# Sensors.net
KiCad netlist of a schematic drawn in Altium Designer
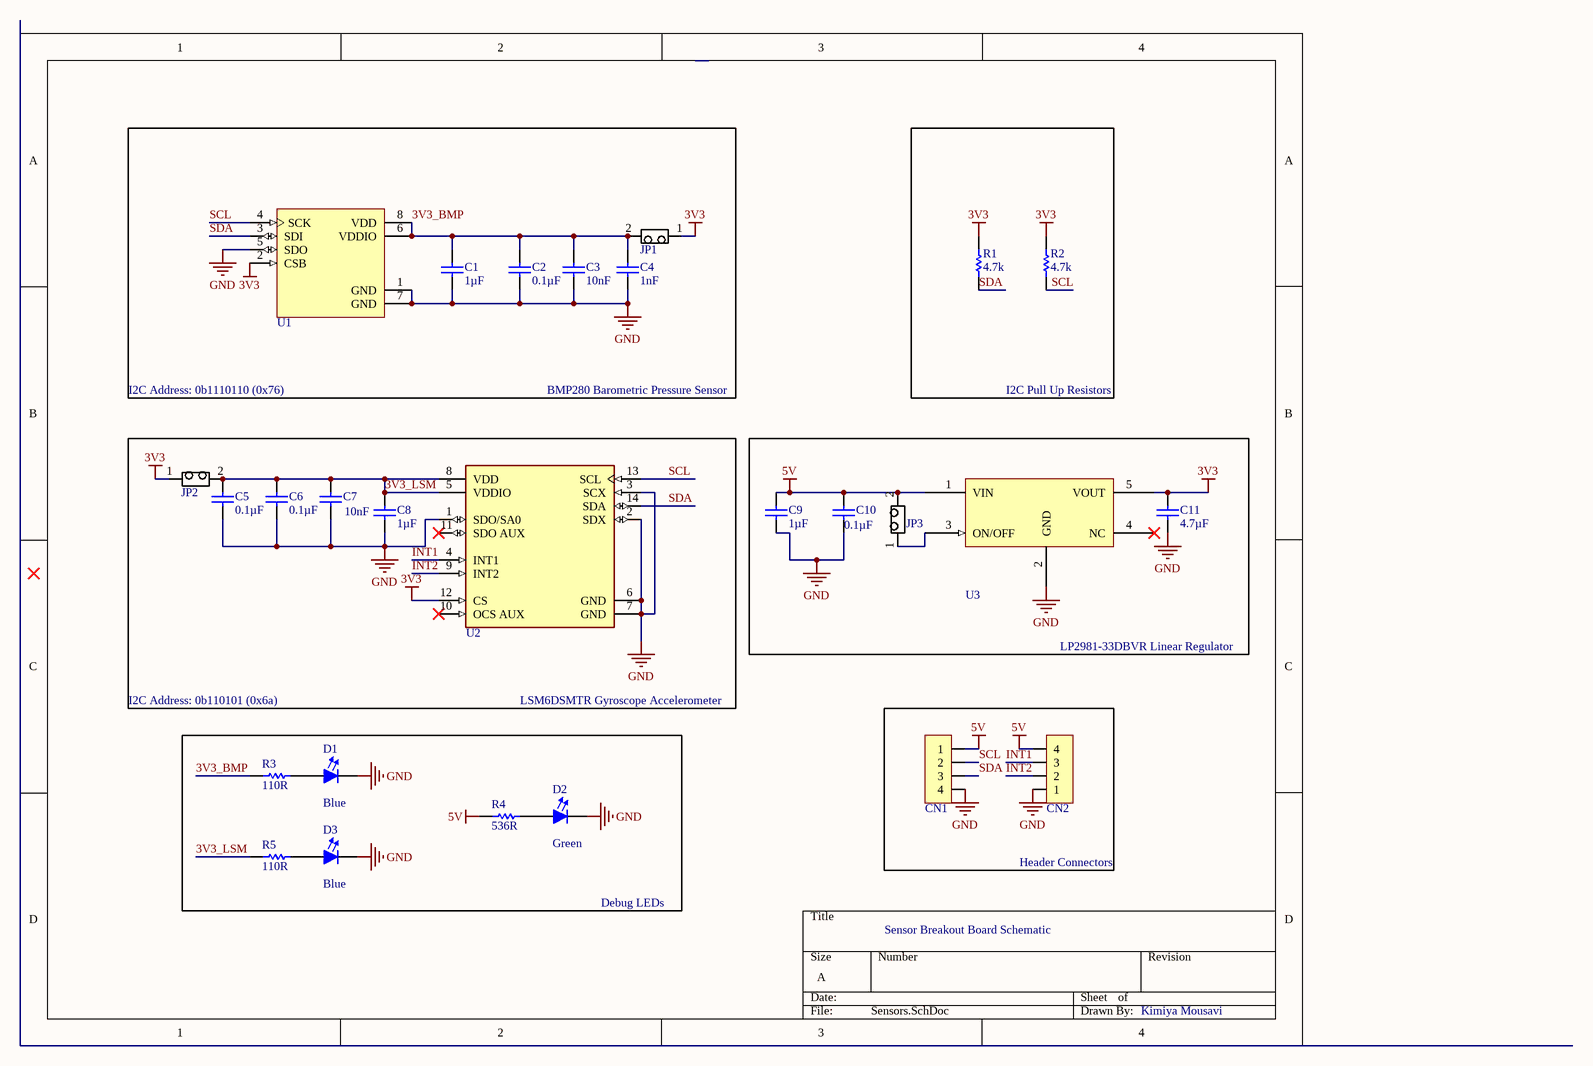
[diagram p0: Sensors.SchDoc]

(export (version "E")
  (design (tool "Eeschema 10.0.6"))
  (components
    (comp (ref "C1")
      (value "1µF")
      (footprint "CAPC1608N(0603\")")
      (description "Capacitor, Ceramic, 25V, +/- 10%, 0603 SMD, X5R")
      (fields
        (field (name "MFG") "Murata-Electronics-North-America")
        (field (name "Comment") "1uF 25V 0603 SMD, Ceramic")
        (field (name "CREATED BY") "Andy Bates")
        (field (name "PUBLISHER") "AUVic")
      )
      (libsource (lib "AUVIC") (part "Symbol"))
    )
    (comp (ref "C2")
      (value "0.1uF, 50V, 10%, X7R, 0603")
      (footprint "CAPC1608N(0603\")")
      (description "0.1µF ±10% Ceramic Capacitor X7R 0603 (1608 Metric)")
      (fields (field (name "CAPACITANCE") "0.1µF") (field (name "CREATED BY") "Poorna Chander Kalidas"))
      (libsource (lib "AUVIC") (part "Symbol"))
    )
    (comp (ref "C3")
      (value "10nF")
      (footprint "CAPC1608N(0603\")")
      (description "Capacitor, Ceramic, 50V, +/- 10%, 0603 SMD")
      (fields
        (field (name "MFG") "Samsung")
        (field (name "Comment") "10 nF, 50V 0603 SMD, Ceramic")
        (field (name "CREATED BY") "Gabriel")
        (field (name "PUBLISHER") "AUVic")
      )
      (libsource (lib "AUVIC") (part "Symbol"))
    )
    (comp (ref "C4")
      (value "1nF")
      (footprint "CAPC1608N(0603\")")
      (description "Capacitor, Ceramic, 50V, +-1%, 0603 SMD, NP0")
      (fields
        (field (name "Comment") "1nF, Ceramic, 50V, +-1%, SMD, NP0")
        (field (name "PUBLISHER") "AUVic")
        (field (name "MADE BY") "Jordan Day")
      )
      (libsource (lib "AUVIC") (part "Symbol"))
    )
    (comp (ref "C5")
      (value "0.1uF, 50V, 10%, X7R, 0603")
      (footprint "CAPC1608N(0603\")")
      (description "0.1µF ±10% Ceramic Capacitor X7R 0603 (1608 Metric)")
      (fields (field (name "CAPACITANCE") "0.1µF") (field (name "CREATED BY") "Poorna Chander Kalidas"))
      (libsource (lib "AUVIC") (part "Symbol"))
    )
    (comp (ref "C6")
      (value "0.1uF, 50V, 10%, X7R, 0603")
      (footprint "CAPC1608N(0603\")")
      (description "0.1µF ±10% Ceramic Capacitor X7R 0603 (1608 Metric)")
      (fields (field (name "CAPACITANCE") "0.1µF") (field (name "CREATED BY") "Poorna Chander Kalidas"))
      (libsource (lib "AUVIC") (part "Symbol"))
    )
    (comp (ref "C7")
      (value "10nF")
      (footprint "CAPC1608N(0603\")")
      (description "Capacitor, Ceramic, 50V, +/- 10%, 0603 SMD")
      (fields
        (field (name "MFG") "Samsung")
        (field (name "Comment") "10 nF, 50V 0603 SMD, Ceramic")
        (field (name "CREATED BY") "Gabriel")
        (field (name "PUBLISHER") "AUVic")
      )
      (libsource (lib "AUVIC") (part "Symbol"))
    )
    (comp (ref "C8")
      (value "1µF")
      (footprint "CAPC1608N(0603\")")
      (description "Capacitor, Ceramic, 25V, +/- 10%, 0603 SMD, X5R")
      (fields
        (field (name "MFG") "Murata-Electronics-North-America")
        (field (name "Comment") "1uF 25V 0603 SMD, Ceramic")
        (field (name "CREATED BY") "Andy Bates")
        (field (name "PUBLISHER") "AUVic")
      )
      (libsource (lib "AUVIC") (part "Symbol"))
    )
    (comp (ref "C9")
      (value "1µF")
      (footprint "CAPC1608N(0603\")")
      (description "Capacitor, Ceramic, 25V, +/- 10%, 0603 SMD, X5R")
      (fields
        (field (name "MFG") "Murata-Electronics-North-America")
        (field (name "Comment") "1uF 25V 0603 SMD, Ceramic")
        (field (name "CREATED BY") "Andy Bates")
        (field (name "PUBLISHER") "AUVic")
      )
      (libsource (lib "AUVIC") (part "Symbol"))
    )
    (comp (ref "C10")
      (value "0.1µF")
      (footprint "CAPC1608N(0603\")")
      (description "Capacitor, Ceramic, 16V, +/- 10%, 0603 SMD, X7R")
      (fields
        (field (name "Comment") "0.1uF 16V 0603 SMD, Ceramic")
        (field (name "CREATED BY") "Andy Bates")
        (field (name "PUBLISHER") "AUVic")
      )
      (libsource (lib "AUVIC") (part "Symbol"))
    )
    (comp (ref "C11")
      (value "4.7µF")
      (footprint "CAPC1608N(0603\")")
      (description "Capacitor, Ceramic, 10V, +/- 10%, 0603 SMD, X5R")
      (fields
        (field (name "MFG") "Samsung")
        (field (name "Comment") "4.7uF 10V 0603 SMD, Ceramic")
        (field (name "CREATED BY") "Ashwin Sira")
        (field (name "PUBLISHER") "AUVic")
      )
      (libsource (lib "AUVIC") (part "Symbol"))
    )
    (comp (ref "CN1")
      (value "Header, Male, 1x4")
      (footprint "Header, Male, 1X4")
      (description "1x4, Pads Pitch: 0.1\" (2.54mm), Through hole")
      (libsource (lib "") (part "Symbol_3"))
    )
    (comp (ref "CN2")
      (value "Header, Male, 1x4")
      (footprint "Header, Male, 1X4")
      (description "1x4, Pads Pitch: 0.1\" (2.54mm), Through hole")
      (libsource (lib "") (part "Symbol_4"))
    )
    (comp (ref "D1")
      (value "LBQ39E-N1OO-35-1")
      (footprint "FP-LB_Q39E-MFG")
      (description "LED BLUE DIFFUSED 0603 SMD")
      (fields (field (name "COLOR") "Blue"))
      (libsource (lib "") (part "Symbol_1"))
    )
    (comp (ref "D2")
      (value "LT Q39G-Q1OO-25-1")
      (footprint "FP-LB_Q39E-MFG")
      (description "LED GREEN DIFFUSED 0603 SMD")
      (fields (field (name "COLOR") "Green"))
      (libsource (lib "") (part "Symbol_1"))
    )
    (comp (ref "D3")
      (value "LBQ39E-N1OO-35-1")
      (footprint "FP-LB_Q39E-MFG")
      (description "LED BLUE DIFFUSED 0603 SMD")
      (fields (field (name "COLOR") "Blue"))
      (libsource (lib "") (part "Symbol_1"))
    )
    (comp (ref "JP1")
      (value "1x2 Male Header")
      (footprint "2X1 Males Header")
      (fields (field (name "MADE BY") "Andy Bates"))
      (libsource (lib "AUVIC") (part "1x2 Male Header"))
    )
    (comp (ref "JP2")
      (value "1x2 Male Header")
      (footprint "2X1 Males Header")
      (fields (field (name "MADE BY") "Andy Bates"))
      (libsource (lib "AUVIC") (part "1x2 Male Header"))
    )
    (comp (ref "JP3")
      (value "1x2 Male Header")
      (footprint "2X1 Males Header")
      (fields (field (name "MADE BY") "Andy Bates"))
      (libsource (lib "AUVIC") (part "1x2 Male Header"))
    )
    (comp (ref "R1")
      (value "4.7k")
      (footprint "RESC1608N(0603\")")
      (description "4.7kR, 1%, 1/8W, 0603 SMD")
      (fields (field (name "MADE BY") "Ashwin Sira"))
      (libsource (lib "") (part "Symbol_2"))
    )
    (comp (ref "R2")
      (value "4.7k")
      (footprint "RESC1608N(0603\")")
      (description "4.7kR, 1%, 1/8W, 0603 SMD")
      (fields (field (name "MADE BY") "Ashwin Sira"))
      (libsource (lib "") (part "Symbol_2"))
    )
    (comp (ref "R3")
      (value "RC0603FR-07110RL")
      (footprint "RESC1608X55X25ML10T15")
      (description "RES SMD 110 OHM 1% 1/10W 0603")
      (fields (field (name "TOLERANCE") "1%") (field (name "RESISTANCE") "110R"))
      (libsource (lib "AUVIC") (part "RES"))
    )
    (comp (ref "R4")
      (value "ERJ-3EKF5360V")
      (footprint "RESC1608X55X30LL15T15")
      (description "SMD Chip Resistor, 0603 [1608 Metric], 536 ohm, ERJ3EK Series, 75 V, Thick Film, 100 mW")
      (fields (field (name "TOLERANCE") "1%") (field (name "RESISTANCE") "536R"))
      (libsource (lib "AUVIC") (part "RES"))
    )
    (comp (ref "R5")
      (value "RC0603FR-07110RL")
      (footprint "RESC1608X55X25ML10T15")
      (description "RES SMD 110 OHM 1% 1/10W 0603")
      (fields (field (name "TOLERANCE") "1%") (field (name "RESISTANCE") "110R"))
      (libsource (lib "AUVIC") (part "RES"))
    )
    (comp (ref "U1")
      (value "BMP280 Barometric Pressure Sensor")
      (footprint "BOSC-LGA-8_V")
      (description "BMP280 Absolute Barometric Pressure Sensor for Battery Powered Devices 2 x 2.5mm")
      (libsource (lib "AUVIC") (part "BOSC-BMP280-LGA-8"))
    )
    (comp (ref "U2")
      (value "LSM6DSMTR, Accelerometer/Gyroscope, LGA-14")
      (footprint "FP-LGA-14L-DM00249496-MFG")
      (description "IMU ACCEL/GYRO I2C/SPI 14LGA")
      (libsource (lib "AUVIC") (part "dd82ae232bae541fa9c740d21cb9072"))
    )
    (comp (ref "U3")
      (value "LP2981-33DBVR")
      (footprint "SOT95P280X145-5N")
      (description "IC REG LINEAR 3.3V 100MA SOT23-5")
      (libsource (lib "AUVIC") (part "LP2981-33DBVR"))
    )
  )
  (nets
    (net (code "1") (name "/3V3_BMP") (class "Default")
      (node (ref "C1") (pin "2") (pinfunction "Cathode_2") (pintype "passive"))
      (node (ref "C2") (pin "2") (pinfunction "Cathode_2") (pintype "passive"))
      (node (ref "C3") (pin "2") (pinfunction "Cathode_2") (pintype "passive"))
      (node (ref "C4") (pin "2") (pinfunction "Cathode_2") (pintype "passive"))
      (node (ref "JP1") (pin "2") (pinfunction "2_2") (pintype "passive"))
      (node (ref "R3") (pin "1") (pinfunction "1_1") (pintype "passive"))
      (node (ref "U1") (pin "6") (pinfunction "VDDIO_6") (pintype "power_in"))
      (node (ref "U1") (pin "8") (pinfunction "VDD_8") (pintype "power_in"))
    )
    (net (code "2") (name "/3V3_LSM") (class "Default")
      (node (ref "C5") (pin "1") (pinfunction "Anode_1") (pintype "passive"))
      (node (ref "C6") (pin "1") (pinfunction "Anode_1") (pintype "passive"))
      (node (ref "C7") (pin "2") (pinfunction "Cathode_2") (pintype "passive"))
      (node (ref "C8") (pin "2") (pinfunction "Cathode_2") (pintype "passive"))
      (node (ref "JP2") (pin "2") (pinfunction "2_2") (pintype "passive"))
      (node (ref "R5") (pin "1") (pinfunction "1_1") (pintype "passive"))
      (node (ref "U2") (pin "5") (pinfunction "VDDIO_5") (pintype "power_in"))
      (node (ref "U2") (pin "8") (pinfunction "VDD_8") (pintype "power_in"))
    )
    (net (code "3") (name "/INT1") (class "Default")
      (node (ref "CN2") (pin "3") (pinfunction "3_3") (pintype "passive"))
      (node (ref "U2") (pin "4") (pinfunction "INT1_4") (pintype "input"))
    )
    (net (code "4") (name "/INT2") (class "Default")
      (node (ref "CN2") (pin "2") (pinfunction "2_2") (pintype "passive"))
      (node (ref "U2") (pin "9") (pinfunction "INT2_9") (pintype "input"))
    )
    (net (code "5") (name "/SCL") (class "Default")
      (node (ref "CN1") (pin "2") (pinfunction "2_2") (pintype "passive"))
      (node (ref "R2") (pin "1") (pinfunction "1_1") (pintype "passive"))
      (node (ref "U1") (pin "4") (pinfunction "SCK_4") (pintype "input"))
      (node (ref "U2") (pin "13") (pinfunction "SCL_13") (pintype "input"))
    )
    (net (code "6") (name "/SDA") (class "Default")
      (node (ref "CN1") (pin "3") (pinfunction "3_3") (pintype "passive"))
      (node (ref "R1") (pin "1") (pinfunction "1_1") (pintype "passive"))
      (node (ref "U1") (pin "3") (pinfunction "SDI_3") (pintype "bidirectional"))
      (node (ref "U2") (pin "14") (pinfunction "SDA_14") (pintype "bidirectional"))
    )
    (net (code "7") (name "3V3") (class "Default")
      (node (ref "C11") (pin "2") (pinfunction "Cathode_2") (pintype "passive"))
      (node (ref "JP1") (pin "1") (pinfunction "1_1") (pintype "passive"))
      (node (ref "JP2") (pin "1") (pinfunction "1_1") (pintype "passive"))
      (node (ref "R1") (pin "2") (pinfunction "2_2") (pintype "passive"))
      (node (ref "R2") (pin "2") (pinfunction "2_2") (pintype "passive"))
      (node (ref "U1") (pin "2") (pinfunction "CSB_2") (pintype "input"))
      (node (ref "U2") (pin "12") (pinfunction "CS_12") (pintype "input"))
      (node (ref "U3") (pin "5") (pinfunction "VOUT_5") (pintype "power_in"))
    )
    (net (code "8") (name "5V") (class "Default")
      (node (ref "C10") (pin "2") (pinfunction "Cathode_2") (pintype "passive"))
      (node (ref "C9") (pin "2") (pinfunction "Cathode_2") (pintype "passive"))
      (node (ref "CN1") (pin "1") (pinfunction "1_1") (pintype "passive"))
      (node (ref "CN2") (pin "4") (pinfunction "4_4") (pintype "passive"))
      (node (ref "JP3") (pin "2") (pinfunction "2_2") (pintype "passive"))
      (node (ref "R4") (pin "1") (pinfunction "1_1") (pintype "passive"))
      (node (ref "U3") (pin "1") (pinfunction "VIN_1") (pintype "power_in"))
    )
    (net (code "9") (name "GND") (class "Default")
      (node (ref "C1") (pin "1") (pinfunction "Anode_1") (pintype "passive"))
      (node (ref "C10") (pin "1") (pinfunction "Anode_1") (pintype "passive"))
      (node (ref "C11") (pin "1") (pinfunction "Anode_1") (pintype "passive"))
      (node (ref "C2") (pin "1") (pinfunction "Anode_1") (pintype "passive"))
      (node (ref "C3") (pin "1") (pinfunction "Anode_1") (pintype "passive"))
      (node (ref "C4") (pin "1") (pinfunction "Anode_1") (pintype "passive"))
      (node (ref "C5") (pin "2") (pinfunction "Cathode_2") (pintype "passive"))
      (node (ref "C6") (pin "2") (pinfunction "Cathode_2") (pintype "passive"))
      (node (ref "C7") (pin "1") (pinfunction "Anode_1") (pintype "passive"))
      (node (ref "C8") (pin "1") (pinfunction "Anode_1") (pintype "passive"))
      (node (ref "C9") (pin "1") (pinfunction "Anode_1") (pintype "passive"))
      (node (ref "CN1") (pin "4") (pinfunction "4_4") (pintype "passive"))
      (node (ref "CN2") (pin "1") (pinfunction "1_1") (pintype "passive"))
      (node (ref "D1") (pin "1") (pinfunction "Cathode_1") (pintype "passive"))
      (node (ref "D2") (pin "1") (pinfunction "Cathode_1") (pintype "passive"))
      (node (ref "D3") (pin "1") (pinfunction "Cathode_1") (pintype "passive"))
      (node (ref "U1") (pin "1") (pinfunction "GND_1") (pintype "power_in"))
      (node (ref "U1") (pin "5") (pinfunction "SDO_5") (pintype "bidirectional"))
      (node (ref "U1") (pin "7") (pinfunction "GND_7") (pintype "power_in"))
      (node (ref "U2") (pin "1") (pinfunction "SDO/SA0_1") (pintype "bidirectional"))
      (node (ref "U2") (pin "2") (pinfunction "SDX_2") (pintype "bidirectional"))
      (node (ref "U2") (pin "3") (pinfunction "SCX_3") (pintype "input"))
      (node (ref "U2") (pin "6") (pinfunction "GND_6") (pintype "power_in"))
      (node (ref "U2") (pin "7") (pinfunction "GND_7") (pintype "power_in"))
      (node (ref "U3") (pin "2") (pinfunction "GND_2") (pintype "power_in"))
    )
    (net (code "10") (name "Net-(D1-Anode)") (class "Default")
      (node (ref "D1") (pin "2") (pinfunction "Anode_2") (pintype "passive"))
      (node (ref "R3") (pin "2") (pinfunction "2_2") (pintype "passive"))
    )
    (net (code "11") (name "Net-(D2-Anode)") (class "Default")
      (node (ref "D2") (pin "2") (pinfunction "Anode_2") (pintype "passive"))
      (node (ref "R4") (pin "2") (pinfunction "2_2") (pintype "passive"))
    )
    (net (code "12") (name "Net-(D3-Anode)") (class "Default")
      (node (ref "D3") (pin "2") (pinfunction "Anode_2") (pintype "passive"))
      (node (ref "R5") (pin "2") (pinfunction "2_2") (pintype "passive"))
    )
    (net (code "13") (name "Net-(U3-ON{slash}OFF)") (class "Default")
      (node (ref "JP3") (pin "1") (pinfunction "1_1") (pintype "passive"))
      (node (ref "U3") (pin "3") (pinfunction "ON/OFF_3") (pintype "input"))
    )
    (net (code "14") (name "unconnected-(U2-OCS_AUX-Pad10)") (class "Default")
      (node (ref "U2") (pin "10") (pinfunction "OCS_AUX_10") (pintype "input+no_connect"))
    )
    (net (code "15") (name "unconnected-(U2-SDO_AUX-Pad11)") (class "Default")
      (node (ref "U2") (pin "11") (pinfunction "SDO_AUX_11") (pintype "bidirectional+no_connect"))
    )
    (net (code "16") (name "unconnected-(U3-NC-Pad4)") (class "Default")
      (node (ref "U3") (pin "4") (pinfunction "NC_4") (pintype "passive+no_connect"))
    )
  )
)
